# PERIPHERALS.net
KiCad netlist of a schematic drawn in Altium Designer
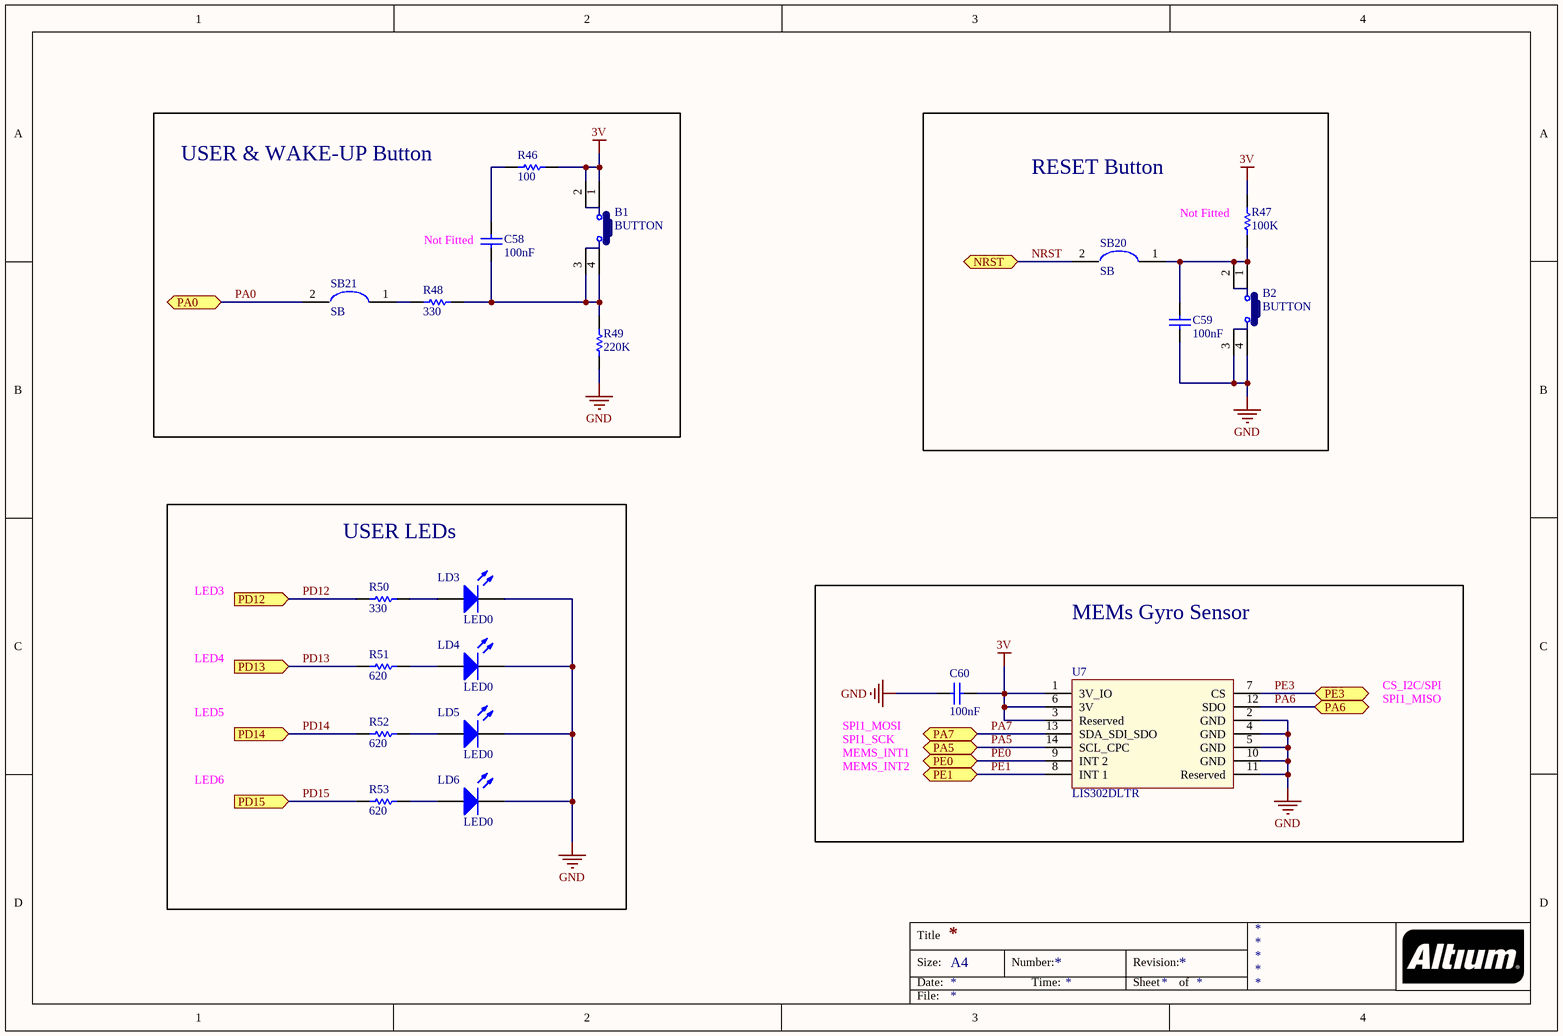
[diagram p0: PERIPHERALS.SchDoc]

(export (version "E")
  (design (tool "Eeschema 10.0.6"))
  (components
    (comp (ref "B1")
      (value "BUTTON")
      (footprint "TL3301PF160QG")
      (fields
        (field (name "MANUFACTURER") "TE Connectivity (Tyco Electronics)")
        (field (name "MANUFACTURER PART NUMBER") "4-1437565-9")
      )
      (libsource (lib "STM32F4DISCOVERY") (part "BUTTON"))
    )
    (comp (ref "B2")
      (value "BUTTON")
      (footprint "TL3301PF160QG")
      (fields
        (field (name "MANUFACTURER") "TE Connectivity (Tyco Electronics)")
        (field (name "MANUFACTURER PART NUMBER") "4-1437565-9")
      )
      (libsource (lib "STM32F4DISCOVERY") (part "BUTTON"))
    )
    (comp (ref "C58")
      (value "100nF")
      (footprint "CAPC0603B")
      (description "Capacitor")
      (fields (field (name "Comment") "Cap") (field (name "PUBLISHER") "Altium Limited"))
      (libsource (lib "STM32F4DISCOVERY") (part "Cap_3"))
    )
    (comp (ref "C59")
      (value "100nF")
      (footprint "CAPC0603B")
      (description "Capacitor")
      (fields (field (name "Comment") "Cap") (field (name "PUBLISHER") "Altium Limited"))
      (libsource (lib "STM32F4DISCOVERY") (part "Cap_3"))
    )
    (comp (ref "C60")
      (value "100nF")
      (footprint "CAPC0603B")
      (description "Capacitor")
      (fields (field (name "Comment") "Cap") (field (name "PUBLISHER") "Altium Limited"))
      (libsource (lib "STM32F4DISCOVERY") (part "Cap_3"))
    )
    (comp (ref "LD3")
      (value "LED0")
      (footprint "LED_0603")
      (description "Typical INFRARED GaAs LED")
      (fields (field (name "PUBLISHER") "Altium Limited"))
      (libsource (lib "STM32F4DISCOVERY") (part "LED0"))
    )
    (comp (ref "LD4")
      (value "LED0")
      (footprint "LED_0603")
      (description "Typical INFRARED GaAs LED")
      (fields (field (name "PUBLISHER") "Altium Limited"))
      (libsource (lib "STM32F4DISCOVERY") (part "LED0"))
    )
    (comp (ref "LD5")
      (value "LED0")
      (footprint "LED_0603")
      (description "Typical INFRARED GaAs LED")
      (fields (field (name "PUBLISHER") "Altium Limited"))
      (libsource (lib "STM32F4DISCOVERY") (part "LED0"))
    )
    (comp (ref "LD6")
      (value "LED0")
      (footprint "LED_0603")
      (description "Typical INFRARED GaAs LED")
      (fields (field (name "PUBLISHER") "Altium Limited"))
      (libsource (lib "STM32F4DISCOVERY") (part "LED0"))
    )
    (comp (ref "R46")
      (value "100")
      (footprint "RESC0402B")
      (description "Resistor")
      (fields (field (name "Comment") "Res1") (field (name "PUBLISHER") "Altium Limited"))
      (libsource (lib "STM32F4DISCOVERY") (part "Res1_4"))
    )
    (comp (ref "R47")
      (value "100K")
      (footprint "RESC0402B")
      (description "Resistor")
      (fields (field (name "Comment") "Res1") (field (name "PUBLISHER") "Altium Limited"))
      (libsource (lib "STM32F4DISCOVERY") (part "Res1_5"))
    )
    (comp (ref "R48")
      (value "330")
      (footprint "RESC0402B")
      (description "Resistor")
      (fields (field (name "Comment") "Res1") (field (name "PUBLISHER") "Altium Limited"))
      (libsource (lib "STM32F4DISCOVERY") (part "Res1_12"))
    )
    (comp (ref "R49")
      (value "220K")
      (footprint "RESC0603B")
      (description "Resistor")
      (fields (field (name "Comment") "Res1") (field (name "PUBLISHER") "Altium Limited"))
      (libsource (lib "STM32F4DISCOVERY") (part "Res1_14"))
    )
    (comp (ref "R50")
      (value "330")
      (footprint "RESC0402B")
      (description "Resistor")
      (fields (field (name "Comment") "Res1") (field (name "PUBLISHER") "Altium Limited"))
      (libsource (lib "STM32F4DISCOVERY") (part "Res1_12"))
    )
    (comp (ref "R51")
      (value "620")
      (footprint "RESC0402B")
      (description "Resistor")
      (fields (field (name "Comment") "Res1") (field (name "PUBLISHER") "Altium Limited"))
      (libsource (lib "STM32F4DISCOVERY") (part "Res1_10"))
    )
    (comp (ref "R52")
      (value "620")
      (footprint "RESC0402B")
      (description "Resistor")
      (fields (field (name "Comment") "Res1") (field (name "PUBLISHER") "Altium Limited"))
      (libsource (lib "STM32F4DISCOVERY") (part "Res1_10"))
    )
    (comp (ref "R53")
      (value "620")
      (footprint "RESC0402B")
      (description "Resistor")
      (fields (field (name "Comment") "Res1") (field (name "PUBLISHER") "Altium Limited"))
      (libsource (lib "STM32F4DISCOVERY") (part "Res1_10"))
    )
    (comp (ref "SB20") (value "SB") (footprint "SB") (libsource (lib "STM32F4DISCOVERY") (part "SB")))
    (comp (ref "SB21") (value "SB") (footprint "SB") (libsource (lib "STM32F4DISCOVERY") (part "SB")))
    (comp (ref "U7")
      (value "LIS302DLTR")
      (footprint "LIS302DLTR")
      (fields (field (name "MANUFACTURER") "STMicroelectronics"))
      (libsource (lib "STM32F4DISCOVERY") (part "LIS302DLTR"))
    )
  )
  (nets
    (net (code "1") (name "/NRST") (class "Default")
      (node (ref "SB20") (pin "2") (pinfunction "2_2") (pintype "passive"))
    )
    (net (code "2") (name "/PA0") (class "Default")
      (node (ref "SB21") (pin "2") (pinfunction "2_2") (pintype "passive"))
    )
    (net (code "3") (name "/PA5") (class "Default")
      (node (ref "U7") (pin "14") (pinfunction "SCL_CPC_14") (pintype "passive"))
    )
    (net (code "4") (name "/PA6") (class "Default")
      (node (ref "U7") (pin "12") (pinfunction "SDO_12") (pintype "passive"))
    )
    (net (code "5") (name "/PA7") (class "Default")
      (node (ref "U7") (pin "13") (pinfunction "SDA_SDI_SDO_13") (pintype "passive"))
    )
    (net (code "6") (name "/PD12") (class "Default")
      (node (ref "R50") (pin "1") (pinfunction "1_1") (pintype "passive"))
    )
    (net (code "7") (name "/PD13") (class "Default")
      (node (ref "R51") (pin "1") (pinfunction "1_1") (pintype "passive"))
    )
    (net (code "8") (name "/PD14") (class "Default")
      (node (ref "R52") (pin "1") (pinfunction "1_1") (pintype "passive"))
    )
    (net (code "9") (name "/PD15") (class "Default")
      (node (ref "R53") (pin "1") (pinfunction "1_1") (pintype "passive"))
    )
    (net (code "10") (name "/PE0") (class "Default")
      (node (ref "U7") (pin "9") (pinfunction "INT_2_9") (pintype "passive"))
    )
    (net (code "11") (name "/PE1") (class "Default")
      (node (ref "U7") (pin "8") (pinfunction "INT_1_8") (pintype "passive"))
    )
    (net (code "12") (name "/PE3") (class "Default")
      (node (ref "U7") (pin "7") (pinfunction "CS_7") (pintype "passive"))
    )
    (net (code "13") (name "3V") (class "Default")
      (node (ref "B1") (pin "1") (pinfunction "1_1") (pintype "passive"))
      (node (ref "B1") (pin "2") (pinfunction "2_2") (pintype "passive"))
      (node (ref "C60") (pin "2") (pinfunction "2_2") (pintype "passive"))
      (node (ref "R46") (pin "1") (pinfunction "1_1") (pintype "passive"))
      (node (ref "R47") (pin "1") (pinfunction "1_1") (pintype "passive"))
      (node (ref "U7") (pin "1") (pinfunction "3V_IO_1") (pintype "passive"))
      (node (ref "U7") (pin "3") (pinfunction "Reserved_3") (pintype "passive"))
      (node (ref "U7") (pin "6") (pinfunction "3V_6") (pintype "passive"))
    )
    (net (code "14") (name "GND") (class "Default")
      (node (ref "B2") (pin "3") (pinfunction "3_3") (pintype "passive"))
      (node (ref "B2") (pin "4") (pinfunction "4_4") (pintype "passive"))
      (node (ref "C59") (pin "2") (pinfunction "2_2") (pintype "passive"))
      (node (ref "C60") (pin "1") (pinfunction "1_1") (pintype "passive"))
      (node (ref "LD3") (pin "2") (pinfunction "K_2") (pintype "passive"))
      (node (ref "LD4") (pin "2") (pinfunction "K_2") (pintype "passive"))
      (node (ref "LD5") (pin "2") (pinfunction "K_2") (pintype "passive"))
      (node (ref "LD6") (pin "2") (pinfunction "K_2") (pintype "passive"))
      (node (ref "R49") (pin "1") (pinfunction "1_1") (pintype "passive"))
      (node (ref "U7") (pin "10") (pinfunction "GND_10") (pintype "passive"))
      (node (ref "U7") (pin "11") (pinfunction "Reserved_11") (pintype "passive"))
      (node (ref "U7") (pin "2") (pinfunction "GND_2") (pintype "passive"))
      (node (ref "U7") (pin "4") (pinfunction "GND_4") (pintype "passive"))
      (node (ref "U7") (pin "5") (pinfunction "GND_5") (pintype "passive"))
    )
    (net (code "15") (name "Net-(B1-Pad3)") (class "Default")
      (node (ref "B1") (pin "3") (pinfunction "3_3") (pintype "passive"))
      (node (ref "B1") (pin "4") (pinfunction "4_4") (pintype "passive"))
      (node (ref "C58") (pin "1") (pinfunction "1_1") (pintype "passive"))
      (node (ref "R48") (pin "2") (pinfunction "2_2") (pintype "passive"))
      (node (ref "R49") (pin "2") (pinfunction "2_2") (pintype "passive"))
    )
    (net (code "16") (name "Net-(B2-Pad1)") (class "Default")
      (node (ref "B2") (pin "1") (pinfunction "1_1") (pintype "passive"))
      (node (ref "B2") (pin "2") (pinfunction "2_2") (pintype "passive"))
      (node (ref "C59") (pin "1") (pinfunction "1_1") (pintype "passive"))
      (node (ref "R47") (pin "2") (pinfunction "2_2") (pintype "passive"))
      (node (ref "SB20") (pin "1") (pinfunction "1_1") (pintype "passive"))
    )
    (net (code "17") (name "Net-(C58-Pad2)") (class "Default")
      (node (ref "C58") (pin "2") (pinfunction "2_2") (pintype "passive"))
      (node (ref "R46") (pin "2") (pinfunction "2_2") (pintype "passive"))
    )
    (net (code "18") (name "Net-(LD3-A)") (class "Default")
      (node (ref "LD3") (pin "1") (pinfunction "A_1") (pintype "passive"))
      (node (ref "R50") (pin "2") (pinfunction "2_2") (pintype "passive"))
    )
    (net (code "19") (name "Net-(LD4-A)") (class "Default")
      (node (ref "LD4") (pin "1") (pinfunction "A_1") (pintype "passive"))
      (node (ref "R51") (pin "2") (pinfunction "2_2") (pintype "passive"))
    )
    (net (code "20") (name "Net-(LD5-A)") (class "Default")
      (node (ref "LD5") (pin "1") (pinfunction "A_1") (pintype "passive"))
      (node (ref "R52") (pin "2") (pinfunction "2_2") (pintype "passive"))
    )
    (net (code "21") (name "Net-(LD6-A)") (class "Default")
      (node (ref "LD6") (pin "1") (pinfunction "A_1") (pintype "passive"))
      (node (ref "R53") (pin "2") (pinfunction "2_2") (pintype "passive"))
    )
    (net (code "22") (name "Net-(R48-Pad1)") (class "Default")
      (node (ref "R48") (pin "1") (pinfunction "1_1") (pintype "passive"))
      (node (ref "SB21") (pin "1") (pinfunction "1_1") (pintype "passive"))
    )
  )
)
